# TestPressureSensor.net
KiCad netlist of a schematic drawn in EAGLE
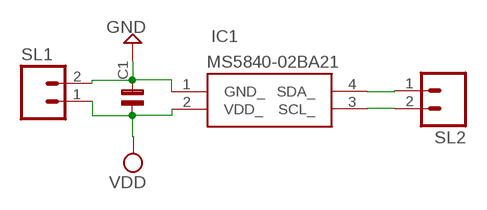
[diagram p0: schematic, sheet 1]

(export (version "E")
  (design (tool "Eeschema 10.0.6"))
  (components
    (comp (ref "C1")
      (value "C0805")
      (footprint "eagle-import:0805")
      (libsource (lib "eagle-import") (part "C0805"))
    )
    (comp (ref "IC1")
      (value "MS5840-02BA21")
      (footprint "eagle-import:MS584002BA21")
      (fields (field (name "TE_INTERNAL_PART_NUMBER") "20000980-00"))
      (libsource (lib "eagle-import") (part "MS5840-02BA21"))
    )
    (comp (ref "SL1")
      (value "M02")
      (footprint "eagle-import:02P")
      (libsource (lib "eagle-import") (part "M02"))
    )
    (comp (ref "SL2")
      (value "M02")
      (footprint "eagle-import:02P")
      (libsource (lib "eagle-import") (part "M02"))
    )
  )
  (nets
    (net (code "1") (name "GND") (class "Default")
      (node (ref "C1") (pin "2") (pinfunction "2_2") (pintype "passive"))
      (node (ref "IC1") (pin "1") (pinfunction "GND__1") (pintype "bidirectional"))
      (node (ref "SL1") (pin "2") (pinfunction "2_2") (pintype "passive"))
    )
    (net (code "2") (name "Net-(IC1-SCL_)") (class "Default")
      (node (ref "IC1") (pin "3") (pinfunction "SCL__3") (pintype "bidirectional"))
      (node (ref "SL2") (pin "2") (pinfunction "2_2") (pintype "passive"))
    )
    (net (code "3") (name "Net-(IC1-SDA_)") (class "Default")
      (node (ref "IC1") (pin "4") (pinfunction "SDA__4") (pintype "bidirectional"))
      (node (ref "SL2") (pin "1") (pinfunction "1_1") (pintype "passive"))
    )
    (net (code "4") (name "VDD") (class "Default")
      (node (ref "C1") (pin "1") (pinfunction "1_1") (pintype "passive"))
      (node (ref "IC1") (pin "2") (pinfunction "VDD__2") (pintype "bidirectional"))
      (node (ref "SL1") (pin "1") (pinfunction "1_1") (pintype "passive"))
    )
  )
)
